# main.net
KiCad netlist of a schematic drawn in Altium Designer
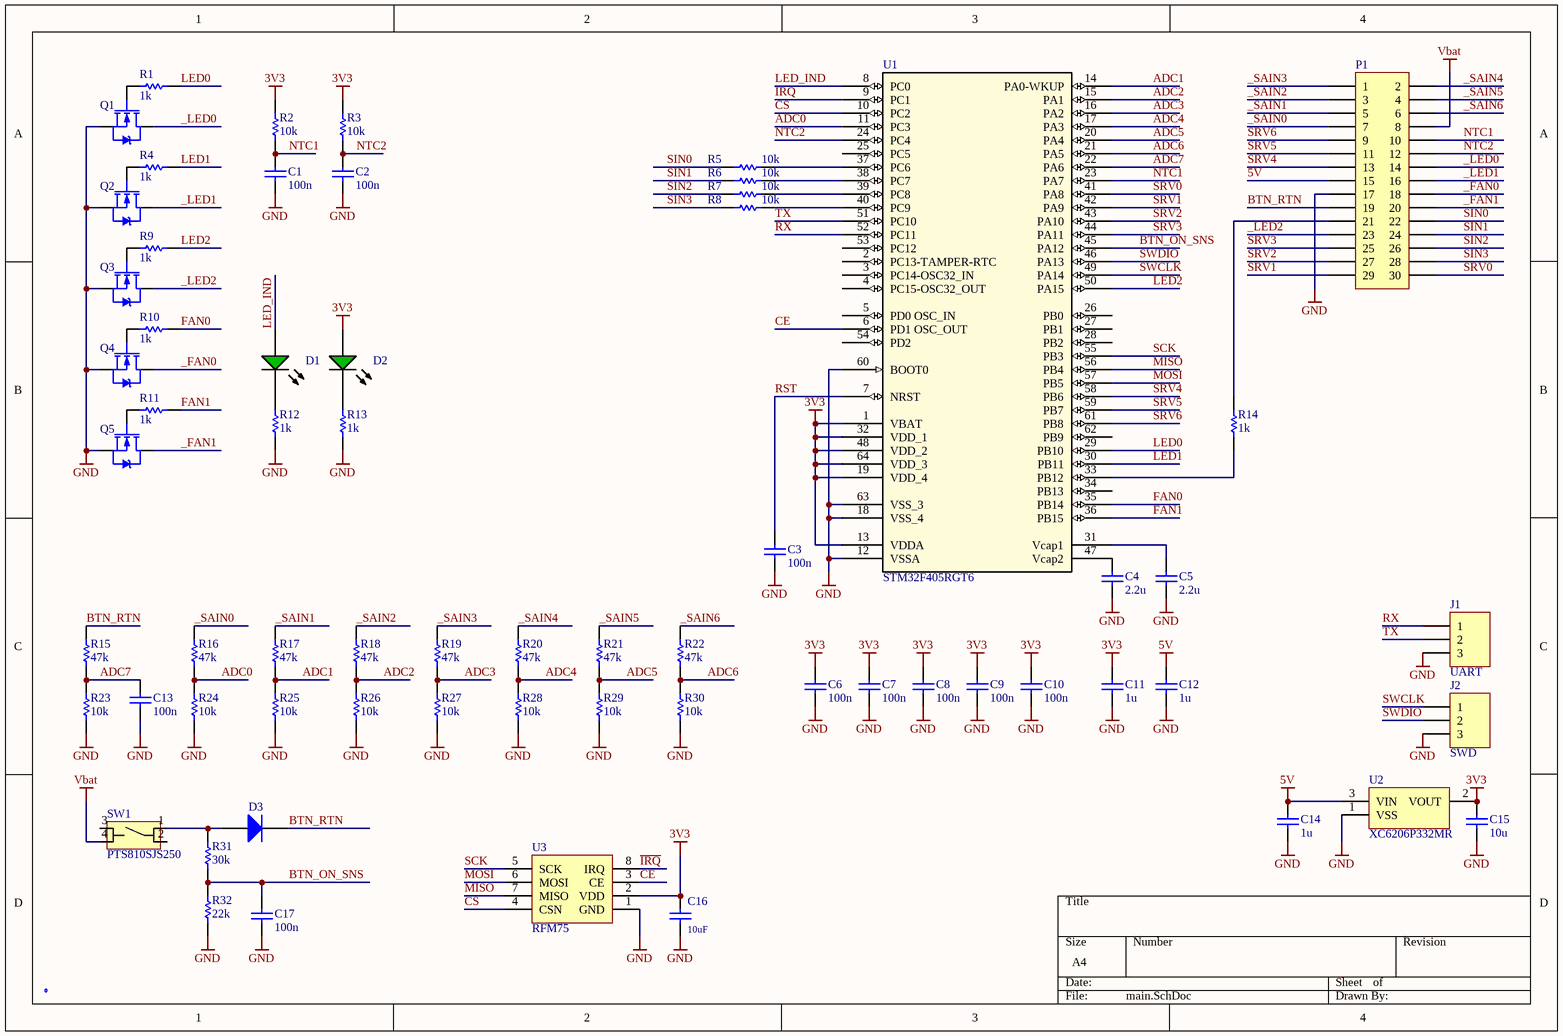
[diagram p0: main.SchDoc]

(export (version "E")
  (design (tool "Eeschema 10.0.6"))
  (components
    (comp (ref "C1")
      (value "100n")
      (footprint "C0603")
      (libsource (lib "Miscellaneous Devices") (part "Cap"))
    )
    (comp (ref "C2")
      (value "100n")
      (footprint "C0603")
      (libsource (lib "Miscellaneous Devices") (part "Cap"))
    )
    (comp (ref "C3")
      (value "100n")
      (footprint "C0402")
      (libsource (lib "Miscellaneous Devices") (part "Cap"))
    )
    (comp (ref "C4")
      (value "2.2u")
      (footprint "C0603")
      (libsource (lib "Miscellaneous Devices") (part "Cap"))
    )
    (comp (ref "C5")
      (value "2.2u")
      (footprint "C0603")
      (libsource (lib "Miscellaneous Devices") (part "Cap"))
    )
    (comp (ref "C6")
      (value "100n")
      (footprint "C0402")
      (libsource (lib "Miscellaneous Devices") (part "Cap"))
    )
    (comp (ref "C7")
      (value "100n")
      (footprint "C0402")
      (libsource (lib "Miscellaneous Devices") (part "Cap"))
    )
    (comp (ref "C8")
      (value "100n")
      (footprint "C0402")
      (libsource (lib "Miscellaneous Devices") (part "Cap"))
    )
    (comp (ref "C9")
      (value "100n")
      (footprint "C0402")
      (libsource (lib "Miscellaneous Devices") (part "Cap"))
    )
    (comp (ref "C10")
      (value "100n")
      (footprint "C0402")
      (libsource (lib "Miscellaneous Devices") (part "Cap"))
    )
    (comp (ref "C11") (value "1u") (footprint "C0603") (libsource (lib "Miscellaneous Devices") (part "Cap")))
    (comp (ref "C12") (value "1u") (footprint "C0603") (libsource (lib "Miscellaneous Devices") (part "Cap")))
    (comp (ref "C13")
      (value "100n")
      (footprint "C0402")
      (libsource (lib "Miscellaneous Devices") (part "Cap"))
    )
    (comp (ref "C14") (value "1u") (footprint "C1210") (libsource (lib "Miscellaneous Devices") (part "Cap")))
    (comp (ref "C15")
      (value "10u")
      (footprint "C1210")
      (libsource (lib "Miscellaneous Devices") (part "Cap"))
    )
    (comp (ref "C16")
      (value "10uF")
      (footprint "C0805")
      (libsource (lib "Miscellaneous Devices") (part "CAP"))
    )
    (comp (ref "C17")
      (value "100n")
      (footprint "C0402")
      (libsource (lib "Miscellaneous Devices") (part "Cap"))
    )
    (comp (ref "D1")
      (value "GRN")
      (footprint "LED-0603-GRN")
      (description "LED 0603 GRN")
      (fields (field (name "LCSC PART NUMBER") "C434420"))
      (libsource (lib "Miscellaneous Devices") (part "LED-0603-GREEN"))
    )
    (comp (ref "D2")
      (value "GRN")
      (footprint "LED-0603-GRN")
      (description "LED 0603 GRN")
      (fields (field (name "LCSC PART NUMBER") "C434420"))
      (libsource (lib "Miscellaneous Devices") (part "LED-0603-GREEN"))
    )
    (comp (ref "D3")
      (value "DS1M")
      (footprint "SOD-123FL")
      (libsource (lib "Miscellaneous Devices") (part "US1M-13-F"))
    )
    (comp (ref "J1")
      (value "UART")
      (footprint "HDR-1x3-P1.25")
      (libsource (lib "Miscellaneous Devices") (part "Header 3"))
    )
    (comp (ref "J2")
      (value "SWD")
      (footprint "HDR-1x3-P1.25")
      (libsource (lib "Miscellaneous Devices") (part "Header 3"))
    )
    (comp (ref "LOGO1") (value "LOGO") (footprint "LOGO") (libsource (lib "Schlib1") (part "LOGO")))
    (comp (ref "P1")
      (value "Header 15X2")
      (footprint "HDR2X15-2mm")
      (description "Header, 15-Pin, Dual row")
      (libsource (lib "Miscellaneous Connectors") (part "Header 15X2"))
    )
    (comp (ref "Q1")
      (value "IRLML2502")
      (footprint "SOT-23")
      (description "MOSFET N-CH 20V 4.2A SOT-23-3")
      (libsource (lib "RozumLibrary") (part "IRLML2502"))
    )
    (comp (ref "Q2")
      (value "IRLML2502")
      (footprint "SOT-23")
      (description "MOSFET N-CH 20V 4.2A SOT-23-3")
      (libsource (lib "RozumLibrary") (part "IRLML2502"))
    )
    (comp (ref "Q3")
      (value "IRLML2502")
      (footprint "SOT-23")
      (description "MOSFET N-CH 20V 4.2A SOT-23-3")
      (libsource (lib "RozumLibrary") (part "IRLML2502"))
    )
    (comp (ref "Q4")
      (value "IRLML2502")
      (footprint "SOT-23")
      (description "MOSFET N-CH 20V 4.2A SOT-23-3")
      (libsource (lib "RozumLibrary") (part "IRLML2502"))
    )
    (comp (ref "Q5")
      (value "IRLML2502")
      (footprint "SOT-23")
      (description "MOSFET N-CH 20V 4.2A SOT-23-3")
      (libsource (lib "RozumLibrary") (part "IRLML2502"))
    )
    (comp (ref "R1") (value "1k") (footprint "R0603") (libsource (lib "Miscellaneous Devices") (part "Res1")))
    (comp (ref "R2")
      (value "10k")
      (footprint "R0603")
      (libsource (lib "Miscellaneous Devices") (part "Res1"))
    )
    (comp (ref "R3")
      (value "10k")
      (footprint "R0603")
      (libsource (lib "Miscellaneous Devices") (part "Res1"))
    )
    (comp (ref "R4") (value "1k") (footprint "R0603") (libsource (lib "Miscellaneous Devices") (part "Res1")))
    (comp (ref "R5")
      (value "10k")
      (footprint "R0603")
      (libsource (lib "Miscellaneous Devices") (part "Res1"))
    )
    (comp (ref "R6")
      (value "10k")
      (footprint "R0603")
      (libsource (lib "Miscellaneous Devices") (part "Res1"))
    )
    (comp (ref "R7")
      (value "10k")
      (footprint "R0603")
      (libsource (lib "Miscellaneous Devices") (part "Res1"))
    )
    (comp (ref "R8")
      (value "10k")
      (footprint "R0603")
      (libsource (lib "Miscellaneous Devices") (part "Res1"))
    )
    (comp (ref "R9") (value "1k") (footprint "R0603") (libsource (lib "Miscellaneous Devices") (part "Res1")))
    (comp (ref "R10")
      (value "1k")
      (footprint "R0603")
      (libsource (lib "Miscellaneous Devices") (part "Res1"))
    )
    (comp (ref "R11")
      (value "1k")
      (footprint "R0603")
      (libsource (lib "Miscellaneous Devices") (part "Res1"))
    )
    (comp (ref "R12")
      (value "1k")
      (footprint "R0603")
      (libsource (lib "Miscellaneous Devices") (part "Res1"))
    )
    (comp (ref "R13")
      (value "1k")
      (footprint "R0603")
      (libsource (lib "Miscellaneous Devices") (part "Res1"))
    )
    (comp (ref "R14")
      (value "1k")
      (footprint "R0603")
      (libsource (lib "Miscellaneous Devices") (part "Res1"))
    )
    (comp (ref "R15")
      (value "47k")
      (footprint "R0603")
      (libsource (lib "Miscellaneous Devices") (part "Res1"))
    )
    (comp (ref "R16")
      (value "47k")
      (footprint "R0402")
      (libsource (lib "Miscellaneous Devices") (part "Res1"))
    )
    (comp (ref "R17")
      (value "47k")
      (footprint "R0402")
      (libsource (lib "Miscellaneous Devices") (part "Res1"))
    )
    (comp (ref "R18")
      (value "47k")
      (footprint "R0402")
      (libsource (lib "Miscellaneous Devices") (part "Res1"))
    )
    (comp (ref "R19")
      (value "47k")
      (footprint "R0402")
      (libsource (lib "Miscellaneous Devices") (part "Res1"))
    )
    (comp (ref "R20")
      (value "47k")
      (footprint "R0402")
      (libsource (lib "Miscellaneous Devices") (part "Res1"))
    )
    (comp (ref "R21")
      (value "47k")
      (footprint "R0603")
      (libsource (lib "Miscellaneous Devices") (part "Res1"))
    )
    (comp (ref "R22")
      (value "47k")
      (footprint "R0603")
      (libsource (lib "Miscellaneous Devices") (part "Res1"))
    )
    (comp (ref "R23")
      (value "10k")
      (footprint "R0603")
      (libsource (lib "Miscellaneous Devices") (part "Res1"))
    )
    (comp (ref "R24")
      (value "10k")
      (footprint "R0402")
      (libsource (lib "Miscellaneous Devices") (part "Res1"))
    )
    (comp (ref "R25")
      (value "10k")
      (footprint "R0402")
      (libsource (lib "Miscellaneous Devices") (part "Res1"))
    )
    (comp (ref "R26")
      (value "10k")
      (footprint "R0402")
      (libsource (lib "Miscellaneous Devices") (part "Res1"))
    )
    (comp (ref "R27")
      (value "10k")
      (footprint "R0402")
      (libsource (lib "Miscellaneous Devices") (part "Res1"))
    )
    (comp (ref "R28")
      (value "10k")
      (footprint "R0402")
      (libsource (lib "Miscellaneous Devices") (part "Res1"))
    )
    (comp (ref "R29")
      (value "10k")
      (footprint "R0603")
      (libsource (lib "Miscellaneous Devices") (part "Res1"))
    )
    (comp (ref "R30")
      (value "10k")
      (footprint "R0603")
      (libsource (lib "Miscellaneous Devices") (part "Res1"))
    )
    (comp (ref "R31")
      (value "30k")
      (footprint "R0603")
      (libsource (lib "Miscellaneous Devices") (part "Res1"))
    )
    (comp (ref "R32")
      (value "22k")
      (footprint "R0603")
      (libsource (lib "Miscellaneous Devices") (part "Res1"))
    )
    (comp (ref "SW1")
      (value "PTS810SJS250")
      (footprint "BTN_PTS810")
      (fields (field (name "LCSC PART NUMBER") "C221896"))
      (libsource (lib "Miscellaneous Devices") (part "Component_1"))
    )
    (comp (ref "U1")
      (value "STM32F405RGT6")
      (footprint "LQFP-64")
      (description "MCU STM32F405RGT6")
      (libsource (lib "RozumLibrary") (part "STM32F405RGT6"))
    )
    (comp (ref "U2")
      (value "XC6206P332MR")
      (footprint "SOT-23")
      (fields (field (name "LCSC PART NUMBER") "C347376"))
      (libsource (lib "Schlib1") (part "Component_4_1"))
    )
    (comp (ref "U3") (value "RFM75") (footprint "RFM75") (libsource (lib "Schlib1") (part "RFM75")))
  )
  (nets
    (net (code "1") (name "/ADC0") (class "Default")
      (node (ref "R16") (pin "1") (pinfunction "1_1") (pintype "passive"))
      (node (ref "R24") (pin "2") (pinfunction "2_2") (pintype "passive"))
      (node (ref "U1") (pin "11") (pinfunction "PC3_11") (pintype "bidirectional"))
    )
    (net (code "2") (name "/ADC1") (class "Default")
      (node (ref "R17") (pin "1") (pinfunction "1_1") (pintype "passive"))
      (node (ref "R25") (pin "2") (pinfunction "2_2") (pintype "passive"))
      (node (ref "U1") (pin "14") (pinfunction "PA0-WKUP_14") (pintype "bidirectional"))
    )
    (net (code "3") (name "/ADC2") (class "Default")
      (node (ref "R18") (pin "1") (pinfunction "1_1") (pintype "passive"))
      (node (ref "R26") (pin "2") (pinfunction "2_2") (pintype "passive"))
      (node (ref "U1") (pin "15") (pinfunction "PA1_15") (pintype "bidirectional"))
    )
    (net (code "4") (name "/ADC3") (class "Default")
      (node (ref "R19") (pin "1") (pinfunction "1_1") (pintype "passive"))
      (node (ref "R27") (pin "2") (pinfunction "2_2") (pintype "passive"))
      (node (ref "U1") (pin "16") (pinfunction "PA2_16") (pintype "bidirectional"))
    )
    (net (code "5") (name "/ADC4") (class "Default")
      (node (ref "R20") (pin "1") (pinfunction "1_1") (pintype "passive"))
      (node (ref "R28") (pin "2") (pinfunction "2_2") (pintype "passive"))
      (node (ref "U1") (pin "17") (pinfunction "PA3_17") (pintype "bidirectional"))
    )
    (net (code "6") (name "/ADC5") (class "Default")
      (node (ref "R21") (pin "1") (pinfunction "1_1") (pintype "passive"))
      (node (ref "R29") (pin "2") (pinfunction "2_2") (pintype "passive"))
      (node (ref "U1") (pin "20") (pinfunction "PA4_20") (pintype "bidirectional"))
    )
    (net (code "7") (name "/ADC6") (class "Default")
      (node (ref "R22") (pin "1") (pinfunction "1_1") (pintype "passive"))
      (node (ref "R30") (pin "2") (pinfunction "2_2") (pintype "passive"))
      (node (ref "U1") (pin "21") (pinfunction "PA5_21") (pintype "bidirectional"))
    )
    (net (code "8") (name "/ADC7") (class "Default")
      (node (ref "C13") (pin "2") (pinfunction "2_2") (pintype "passive"))
      (node (ref "R15") (pin "1") (pinfunction "1_1") (pintype "passive"))
      (node (ref "R23") (pin "2") (pinfunction "2_2") (pintype "passive"))
      (node (ref "U1") (pin "22") (pinfunction "PA6_22") (pintype "bidirectional"))
    )
    (net (code "9") (name "/BTN_ON_SNS") (class "Default")
      (node (ref "C17") (pin "2") (pinfunction "2_2") (pintype "passive"))
      (node (ref "R31") (pin "1") (pinfunction "1_1") (pintype "passive"))
      (node (ref "R32") (pin "2") (pinfunction "2_2") (pintype "passive"))
      (node (ref "U1") (pin "45") (pinfunction "PA12_45") (pintype "bidirectional"))
    )
    (net (code "10") (name "/BTN_RTN") (class "Default")
      (node (ref "D3") (pin "2") (pinfunction "K_2") (pintype "passive"))
      (node (ref "P1") (pin "19") (pinfunction "19_19") (pintype "passive"))
      (node (ref "R15") (pin "2") (pinfunction "2_2") (pintype "passive"))
    )
    (net (code "11") (name "/CE") (class "Default")
      (node (ref "U1") (pin "6") (pinfunction "PD1_OSC_OUT_6") (pintype "bidirectional"))
      (node (ref "U3") (pin "3") (pinfunction "CE_3") (pintype "passive"))
    )
    (net (code "12") (name "/FAN0") (class "Default")
      (node (ref "R10") (pin "2") (pinfunction "2_2") (pintype "passive"))
      (node (ref "U1") (pin "35") (pinfunction "PB14_35") (pintype "bidirectional"))
    )
    (net (code "13") (name "/FAN1") (class "Default")
      (node (ref "R11") (pin "2") (pinfunction "2_2") (pintype "passive"))
      (node (ref "U1") (pin "36") (pinfunction "PB15_36") (pintype "bidirectional"))
    )
    (net (code "14") (name "/LED0") (class "Default")
      (node (ref "R1") (pin "2") (pinfunction "2_2") (pintype "passive"))
      (node (ref "U1") (pin "29") (pinfunction "PB10_29") (pintype "bidirectional"))
    )
    (net (code "15") (name "/LED1") (class "Default")
      (node (ref "R4") (pin "2") (pinfunction "2_2") (pintype "passive"))
      (node (ref "U1") (pin "30") (pinfunction "PB11_30") (pintype "bidirectional"))
    )
    (net (code "16") (name "/LED2") (class "Default")
      (node (ref "R9") (pin "2") (pinfunction "2_2") (pintype "passive"))
      (node (ref "U1") (pin "50") (pinfunction "PA15_50") (pintype "bidirectional"))
    )
    (net (code "17") (name "/LED_IND") (class "Default")
      (node (ref "D1") (pin "1") (pinfunction "A_1") (pintype "passive"))
      (node (ref "U1") (pin "8") (pinfunction "PC0_8") (pintype "bidirectional"))
    )
    (net (code "18") (name "/MISO") (class "Default")
      (node (ref "U1") (pin "56") (pinfunction "PB4_56") (pintype "bidirectional"))
      (node (ref "U3") (pin "7") (pinfunction "MISO_7") (pintype "passive"))
    )
    (net (code "19") (name "/MOSI") (class "Default")
      (node (ref "U1") (pin "57") (pinfunction "PB5_57") (pintype "bidirectional"))
      (node (ref "U3") (pin "6") (pinfunction "MOSI_6") (pintype "passive"))
    )
    (net (code "20") (name "/NTC1") (class "Default")
      (node (ref "C1") (pin "2") (pinfunction "2_2") (pintype "passive"))
      (node (ref "P1") (pin "10") (pinfunction "10_10") (pintype "passive"))
      (node (ref "R2") (pin "1") (pinfunction "1_1") (pintype "passive"))
      (node (ref "U1") (pin "23") (pinfunction "PA7_23") (pintype "bidirectional"))
    )
    (net (code "21") (name "/NTC2") (class "Default")
      (node (ref "C2") (pin "2") (pinfunction "2_2") (pintype "passive"))
      (node (ref "P1") (pin "12") (pinfunction "12_12") (pintype "passive"))
      (node (ref "R3") (pin "1") (pinfunction "1_1") (pintype "passive"))
      (node (ref "U1") (pin "24") (pinfunction "PC4_24") (pintype "bidirectional"))
    )
    (net (code "22") (name "/RST") (class "Default")
      (node (ref "C3") (pin "2") (pinfunction "2_2") (pintype "passive"))
      (node (ref "U1") (pin "7") (pinfunction "NRST_7") (pintype "bidirectional"))
    )
    (net (code "23") (name "/RX") (class "Default")
      (node (ref "J1") (pin "1") (pinfunction "1_1") (pintype "passive"))
      (node (ref "U1") (pin "52") (pinfunction "PC11_52") (pintype "bidirectional"))
    )
    (net (code "24") (name "/SCK") (class "Default")
      (node (ref "U1") (pin "55") (pinfunction "PB3_55") (pintype "bidirectional"))
      (node (ref "U3") (pin "5") (pinfunction "SCK_5") (pintype "passive"))
    )
    (net (code "25") (name "/SIN0") (class "Default")
      (node (ref "P1") (pin "22") (pinfunction "22_22") (pintype "passive"))
      (node (ref "R5") (pin "2") (pinfunction "2_2") (pintype "passive"))
    )
    (net (code "26") (name "/SIN1") (class "Default")
      (node (ref "P1") (pin "24") (pinfunction "24_24") (pintype "passive"))
      (node (ref "R6") (pin "2") (pinfunction "2_2") (pintype "passive"))
    )
    (net (code "27") (name "/SIN2") (class "Default")
      (node (ref "P1") (pin "26") (pinfunction "26_26") (pintype "passive"))
      (node (ref "R7") (pin "2") (pinfunction "2_2") (pintype "passive"))
    )
    (net (code "28") (name "/SIN3") (class "Default")
      (node (ref "P1") (pin "28") (pinfunction "28_28") (pintype "passive"))
      (node (ref "R8") (pin "2") (pinfunction "2_2") (pintype "passive"))
    )
    (net (code "29") (name "/SRV0") (class "Default")
      (node (ref "P1") (pin "30") (pinfunction "30_30") (pintype "passive"))
      (node (ref "U1") (pin "41") (pinfunction "PA8_41") (pintype "bidirectional"))
    )
    (net (code "30") (name "/SRV1") (class "Default")
      (node (ref "P1") (pin "29") (pinfunction "29_29") (pintype "passive"))
      (node (ref "U1") (pin "42") (pinfunction "PA9_42") (pintype "bidirectional"))
    )
    (net (code "31") (name "/SRV2") (class "Default")
      (node (ref "P1") (pin "27") (pinfunction "27_27") (pintype "passive"))
      (node (ref "U1") (pin "43") (pinfunction "PA10_43") (pintype "bidirectional"))
    )
    (net (code "32") (name "/SRV3") (class "Default")
      (node (ref "P1") (pin "25") (pinfunction "25_25") (pintype "passive"))
      (node (ref "U1") (pin "44") (pinfunction "PA11_44") (pintype "bidirectional"))
    )
    (net (code "33") (name "/SRV4") (class "Default")
      (node (ref "P1") (pin "13") (pinfunction "13_13") (pintype "passive"))
      (node (ref "U1") (pin "58") (pinfunction "PB6_58") (pintype "bidirectional"))
    )
    (net (code "34") (name "/SRV5") (class "Default")
      (node (ref "P1") (pin "11") (pinfunction "11_11") (pintype "passive"))
      (node (ref "U1") (pin "59") (pinfunction "PB7_59") (pintype "bidirectional"))
    )
    (net (code "35") (name "/SRV6") (class "Default")
      (node (ref "P1") (pin "9") (pinfunction "9_9") (pintype "passive"))
      (node (ref "U1") (pin "61") (pinfunction "PB8_61") (pintype "bidirectional"))
    )
    (net (code "36") (name "/SWCLK") (class "Default")
      (node (ref "J2") (pin "1") (pinfunction "1_1") (pintype "passive"))
      (node (ref "U1") (pin "49") (pinfunction "PA14_49") (pintype "bidirectional"))
    )
    (net (code "37") (name "/SWDIO") (class "Default")
      (node (ref "J2") (pin "2") (pinfunction "2_2") (pintype "passive"))
      (node (ref "U1") (pin "46") (pinfunction "PA13_46") (pintype "bidirectional"))
    )
    (net (code "38") (name "/TX") (class "Default")
      (node (ref "J1") (pin "2") (pinfunction "2_2") (pintype "passive"))
      (node (ref "U1") (pin "51") (pinfunction "PC10_51") (pintype "bidirectional"))
    )
    (net (code "39") (name "/_FAN0") (class "Default")
      (node (ref "P1") (pin "18") (pinfunction "18_18") (pintype "passive"))
      (node (ref "Q4") (pin "3") (pinfunction "D_3") (pintype "passive"))
    )
    (net (code "40") (name "/_FAN1") (class "Default")
      (node (ref "P1") (pin "20") (pinfunction "20_20") (pintype "passive"))
      (node (ref "Q5") (pin "3") (pinfunction "D_3") (pintype "passive"))
    )
    (net (code "41") (name "/_LED0") (class "Default")
      (node (ref "P1") (pin "14") (pinfunction "14_14") (pintype "passive"))
      (node (ref "Q1") (pin "3") (pinfunction "D_3") (pintype "passive"))
    )
    (net (code "42") (name "/_LED1") (class "Default")
      (node (ref "P1") (pin "16") (pinfunction "16_16") (pintype "passive"))
      (node (ref "Q2") (pin "3") (pinfunction "D_3") (pintype "passive"))
    )
    (net (code "43") (name "/_LED2") (class "Default")
      (node (ref "P1") (pin "23") (pinfunction "23_23") (pintype "passive"))
      (node (ref "Q3") (pin "3") (pinfunction "D_3") (pintype "passive"))
    )
    (net (code "44") (name "/_SAIN0") (class "Default")
      (node (ref "P1") (pin "7") (pinfunction "7_7") (pintype "passive"))
      (node (ref "R16") (pin "2") (pinfunction "2_2") (pintype "passive"))
    )
    (net (code "45") (name "/_SAIN1") (class "Default")
      (node (ref "P1") (pin "5") (pinfunction "5_5") (pintype "passive"))
      (node (ref "R17") (pin "2") (pinfunction "2_2") (pintype "passive"))
    )
    (net (code "46") (name "/_SAIN2") (class "Default")
      (node (ref "P1") (pin "3") (pinfunction "3_3") (pintype "passive"))
      (node (ref "R18") (pin "2") (pinfunction "2_2") (pintype "passive"))
    )
    (net (code "47") (name "/_SAIN3") (class "Default")
      (node (ref "P1") (pin "1") (pinfunction "1_1") (pintype "passive"))
      (node (ref "R19") (pin "2") (pinfunction "2_2") (pintype "passive"))
    )
    (net (code "48") (name "/_SAIN4") (class "Default")
      (node (ref "P1") (pin "2") (pinfunction "2_2") (pintype "passive"))
      (node (ref "R20") (pin "2") (pinfunction "2_2") (pintype "passive"))
    )
    (net (code "49") (name "/_SAIN5") (class "Default")
      (node (ref "P1") (pin "4") (pinfunction "4_4") (pintype "passive"))
      (node (ref "R21") (pin "2") (pinfunction "2_2") (pintype "passive"))
    )
    (net (code "50") (name "/_SAIN6") (class "Default")
      (node (ref "P1") (pin "6") (pinfunction "6_6") (pintype "passive"))
      (node (ref "R22") (pin "2") (pinfunction "2_2") (pintype "passive"))
    )
    (net (code "51") (name "/~{CS}") (class "Default")
      (node (ref "U1") (pin "10") (pinfunction "PC2_10") (pintype "bidirectional"))
      (node (ref "U3") (pin "4") (pinfunction "CSN_4") (pintype "passive"))
    )
    (net (code "52") (name "/~{IRQ}") (class "Default")
      (node (ref "U1") (pin "9") (pinfunction "PC1_9") (pintype "bidirectional"))
      (node (ref "U3") (pin "8") (pinfunction "IRQ_8") (pintype "passive"))
    )
    (net (code "53") (name "3V3") (class "Default")
      (node (ref "C10") (pin "2") (pinfunction "2_2") (pintype "passive"))
      (node (ref "C11") (pin "2") (pinfunction "2_2") (pintype "passive"))
      (node (ref "C15") (pin "2") (pinfunction "2_2") (pintype "passive"))
      (node (ref "C16") (pin "2") (pinfunction "2_2") (pintype "passive"))
      (node (ref "C6") (pin "2") (pinfunction "2_2") (pintype "passive"))
      (node (ref "C7") (pin "2") (pinfunction "2_2") (pintype "passive"))
      (node (ref "C8") (pin "2") (pinfunction "2_2") (pintype "passive"))
      (node (ref "C9") (pin "2") (pinfunction "2_2") (pintype "passive"))
      (node (ref "D2") (pin "1") (pinfunction "A_1") (pintype "passive"))
      (node (ref "R2") (pin "2") (pinfunction "2_2") (pintype "passive"))
      (node (ref "R3") (pin "2") (pinfunction "2_2") (pintype "passive"))
      (node (ref "U1") (pin "1") (pinfunction "VBAT_1") (pintype "power_in"))
      (node (ref "U1") (pin "13") (pinfunction "VDDA_13") (pintype "power_in"))
      (node (ref "U1") (pin "19") (pinfunction "VDD_4_19") (pintype "power_in"))
      (node (ref "U1") (pin "32") (pinfunction "VDD_1_32") (pintype "power_in"))
      (node (ref "U1") (pin "48") (pinfunction "VDD_2_48") (pintype "power_in"))
      (node (ref "U1") (pin "64") (pinfunction "VDD_3_64") (pintype "power_in"))
      (node (ref "U2") (pin "2") (pinfunction "VOUT_2") (pintype "passive"))
      (node (ref "U3") (pin "2") (pinfunction "VDD_2") (pintype "passive"))
    )
    (net (code "54") (name "5V") (class "Default")
      (node (ref "C12") (pin "2") (pinfunction "2_2") (pintype "passive"))
      (node (ref "C14") (pin "2") (pinfunction "2_2") (pintype "passive"))
      (node (ref "P1") (pin "15") (pinfunction "15_15") (pintype "passive"))
      (node (ref "U2") (pin "3") (pinfunction "VIN_3") (pintype "passive"))
    )
    (net (code "55") (name "GND") (class "Default")
      (node (ref "C1") (pin "1") (pinfunction "1_1") (pintype "passive"))
      (node (ref "C10") (pin "1") (pinfunction "1_1") (pintype "passive"))
      (node (ref "C11") (pin "1") (pinfunction "1_1") (pintype "passive"))
      (node (ref "C12") (pin "1") (pinfunction "1_1") (pintype "passive"))
      (node (ref "C13") (pin "1") (pinfunction "1_1") (pintype "passive"))
      (node (ref "C14") (pin "1") (pinfunction "1_1") (pintype "passive"))
      (node (ref "C15") (pin "1") (pinfunction "1_1") (pintype "passive"))
      (node (ref "C16") (pin "1") (pinfunction "1_1") (pintype "passive"))
      (node (ref "C17") (pin "1") (pinfunction "1_1") (pintype "passive"))
      (node (ref "C2") (pin "1") (pinfunction "1_1") (pintype "passive"))
      (node (ref "C3") (pin "1") (pinfunction "1_1") (pintype "passive"))
      (node (ref "C4") (pin "1") (pinfunction "1_1") (pintype "passive"))
      (node (ref "C5") (pin "1") (pinfunction "1_1") (pintype "passive"))
      (node (ref "C6") (pin "1") (pinfunction "1_1") (pintype "passive"))
      (node (ref "C7") (pin "1") (pinfunction "1_1") (pintype "passive"))
      (node (ref "C8") (pin "1") (pinfunction "1_1") (pintype "passive"))
      (node (ref "C9") (pin "1") (pinfunction "1_1") (pintype "passive"))
      (node (ref "J1") (pin "3") (pinfunction "3_3") (pintype "passive"))
      (node (ref "J2") (pin "3") (pinfunction "3_3") (pintype "passive"))
      (node (ref "P1") (pin "17") (pinfunction "17_17") (pintype "passive"))
      (node (ref "Q1") (pin "2") (pinfunction "S_2") (pintype "passive"))
      (node (ref "Q2") (pin "2") (pinfunction "S_2") (pintype "passive"))
      (node (ref "Q3") (pin "2") (pinfunction "S_2") (pintype "passive"))
      (node (ref "Q4") (pin "2") (pinfunction "S_2") (pintype "passive"))
      (node (ref "Q5") (pin "2") (pinfunction "S_2") (pintype "passive"))
      (node (ref "R12") (pin "1") (pinfunction "1_1") (pintype "passive"))
      (node (ref "R13") (pin "1") (pinfunction "1_1") (pintype "passive"))
      (node (ref "R23") (pin "1") (pinfunction "1_1") (pintype "passive"))
      (node (ref "R24") (pin "1") (pinfunction "1_1") (pintype "passive"))
      (node (ref "R25") (pin "1") (pinfunction "1_1") (pintype "passive"))
      (node (ref "R26") (pin "1") (pinfunction "1_1") (pintype "passive"))
      (node (ref "R27") (pin "1") (pinfunction "1_1") (pintype "passive"))
      (node (ref "R28") (pin "1") (pinfunction "1_1") (pintype "passive"))
      (node (ref "R29") (pin "1") (pinfunction "1_1") (pintype "passive"))
      (node (ref "R30") (pin "1") (pinfunction "1_1") (pintype "passive"))
      (node (ref "R32") (pin "1") (pinfunction "1_1") (pintype "passive"))
      (node (ref "U1") (pin "12") (pinfunction "VSSA_12") (pintype "power_in"))
      (node (ref "U1") (pin "18") (pinfunction "VSS_4_18") (pintype "power_in"))
      (node (ref "U1") (pin "60") (pinfunction "BOOT0_60") (pintype "input"))
      (node (ref "U1") (pin "63") (pinfunction "VSS_3_63") (pintype "power_in"))
      (node (ref "U2") (pin "1") (pinfunction "VSS_1") (pintype "passive"))
      (node (ref "U3") (pin "1") (pinfunction "GND_1") (pintype "passive"))
    )
    (net (code "56") (name "Net-(D1-K)") (class "Default")
      (node (ref "D1") (pin "2") (pinfunction "K_2") (pintype "passive"))
      (node (ref "R12") (pin "2") (pinfunction "2_2") (pintype "passive"))
    )
    (net (code "57") (name "Net-(D2-K)") (class "Default")
      (node (ref "D2") (pin "2") (pinfunction "K_2") (pintype "passive"))
      (node (ref "R13") (pin "2") (pinfunction "2_2") (pintype "passive"))
    )
    (net (code "58") (name "Net-(D3-A)") (class "Default")
      (node (ref "D3") (pin "1") (pinfunction "A_1") (pintype "passive"))
      (node (ref "R31") (pin "2") (pinfunction "2_2") (pintype "passive"))
      (node (ref "SW1") (pin "1") (pinfunction "1_1") (pintype "passive"))
    )
    (net (code "59") (name "Net-(P1-Pad21)") (class "Default")
      (node (ref "P1") (pin "21") (pinfunction "21_21") (pintype "passive"))
      (node (ref "R14") (pin "2") (pinfunction "2_2") (pintype "passive"))
    )
    (net (code "60") (name "Net-(Q1-G)") (class "Default")
      (node (ref "Q1") (pin "1") (pinfunction "G_1") (pintype "passive"))
      (node (ref "R1") (pin "1") (pinfunction "1_1") (pintype "passive"))
    )
    (net (code "61") (name "Net-(Q2-G)") (class "Default")
      (node (ref "Q2") (pin "1") (pinfunction "G_1") (pintype "passive"))
      (node (ref "R4") (pin "1") (pinfunction "1_1") (pintype "passive"))
    )
    (net (code "62") (name "Net-(Q3-G)") (class "Default")
      (node (ref "Q3") (pin "1") (pinfunction "G_1") (pintype "passive"))
      (node (ref "R9") (pin "1") (pinfunction "1_1") (pintype "passive"))
    )
    (net (code "63") (name "Net-(Q4-G)") (class "Default")
      (node (ref "Q4") (pin "1") (pinfunction "G_1") (pintype "passive"))
      (node (ref "R10") (pin "1") (pinfunction "1_1") (pintype "passive"))
    )
    (net (code "64") (name "Net-(Q5-G)") (class "Default")
      (node (ref "Q5") (pin "1") (pinfunction "G_1") (pintype "passive"))
      (node (ref "R11") (pin "1") (pinfunction "1_1") (pintype "passive"))
    )
    (net (code "65") (name "Net-(U1-PB12)") (class "Default")
      (node (ref "R14") (pin "1") (pinfunction "1_1") (pintype "passive"))
      (node (ref "U1") (pin "33") (pinfunction "PB12_33") (pintype "bidirectional"))
    )
    (net (code "66") (name "Net-(U1-PC6)") (class "Default")
      (node (ref "R5") (pin "1") (pinfunction "1_1") (pintype "passive"))
      (node (ref "U1") (pin "37") (pinfunction "PC6_37") (pintype "bidirectional"))
    )
    (net (code "67") (name "Net-(U1-PC7)") (class "Default")
      (node (ref "R6") (pin "1") (pinfunction "1_1") (pintype "passive"))
      (node (ref "U1") (pin "38") (pinfunction "PC7_38") (pintype "bidirectional"))
    )
    (net (code "68") (name "Net-(U1-PC8)") (class "Default")
      (node (ref "R7") (pin "1") (pinfunction "1_1") (pintype "passive"))
      (node (ref "U1") (pin "39") (pinfunction "PC8_39") (pintype "bidirectional"))
    )
    (net (code "69") (name "Net-(U1-PC9)") (class "Default")
      (node (ref "R8") (pin "1") (pinfunction "1_1") (pintype "passive"))
      (node (ref "U1") (pin "40") (pinfunction "PC9_40") (pintype "bidirectional"))
    )
    (net (code "70") (name "Net-(U1-Vcap1)") (class "Default")
      (node (ref "C5") (pin "2") (pinfunction "2_2") (pintype "passive"))
      (node (ref "U1") (pin "31") (pinfunction "Vcap1_31") (pintype "power_in"))
    )
    (net (code "71") (name "Net-(U1-Vcap2)") (class "Default")
      (node (ref "C4") (pin "2") (pinfunction "2_2") (pintype "passive"))
      (node (ref "U1") (pin "47") (pinfunction "Vcap2_47") (pintype "power_in"))
    )
    (net (code "72") (name "Vbat") (class "Default")
      (node (ref "P1") (pin "8") (pinfunction "8_8") (pintype "passive"))
      (node (ref "SW1") (pin "4") (pinfunction "4_4") (pintype "passive"))
    )
    (net (code "73") (name "unconnected-(SW1-Pad2)") (class "Default")
      (node (ref "SW1") (pin "2") (pinfunction "2_2") (pintype "passive"))
    )
    (net (code "74") (name "unconnected-(SW1-Pad3)") (class "Default")
      (node (ref "SW1") (pin "3") (pinfunction "3_3") (pintype "passive"))
    )
    (net (code "75") (name "unconnected-(U1-PB0-Pad26)") (class "Default")
      (node (ref "U1") (pin "26") (pinfunction "PB0_26") (pintype "bidirectional"))
    )
    (net (code "76") (name "unconnected-(U1-PB1-Pad27)") (class "Default")
      (node (ref "U1") (pin "27") (pinfunction "PB1_27") (pintype "bidirectional"))
    )
    (net (code "77") (name "unconnected-(U1-PB2-Pad28)") (class "Default")
      (node (ref "U1") (pin "28") (pinfunction "PB2_28") (pintype "bidirectional"))
    )
    (net (code "78") (name "unconnected-(U1-PB9-Pad62)") (class "Default")
      (node (ref "U1") (pin "62") (pinfunction "PB9_62") (pintype "bidirectional"))
    )
    (net (code "79") (name "unconnected-(U1-PB13-Pad34)") (class "Default")
      (node (ref "U1") (pin "34") (pinfunction "PB13_34") (pintype "bidirectional"))
    )
    (net (code "80") (name "unconnected-(U1-PC5-Pad25)") (class "Default")
      (node (ref "U1") (pin "25") (pinfunction "PC5_25") (pintype "bidirectional"))
    )
    (net (code "81") (name "unconnected-(U1-PC12-Pad53)") (class "Default")
      (node (ref "U1") (pin "53") (pinfunction "PC12_53") (pintype "bidirectional"))
    )
    (net (code "82") (name "unconnected-(U1-PC13-TAMPER-RTC-Pad2)") (class "Default")
      (node (ref "U1") (pin "2") (pinfunction "PC13-TAMPER-RTC_2") (pintype "bidirectional"))
    )
    (net (code "83") (name "unconnected-(U1-PC14-OSC32_IN-Pad3)") (class "Default")
      (node (ref "U1") (pin "3") (pinfunction "PC14-OSC32_IN_3") (pintype "bidirectional"))
    )
    (net (code "84") (name "unconnected-(U1-PC15-OSC32_OUT-Pad4)") (class "Default")
      (node (ref "U1") (pin "4") (pinfunction "PC15-OSC32_OUT_4") (pintype "bidirectional"))
    )
    (net (code "85") (name "unconnected-(U1-PD0_OSC_IN-Pad5)") (class "Default")
      (node (ref "U1") (pin "5") (pinfunction "PD0_OSC_IN_5") (pintype "bidirectional"))
    )
    (net (code "86") (name "unconnected-(U1-PD2-Pad54)") (class "Default")
      (node (ref "U1") (pin "54") (pinfunction "PD2_54") (pintype "bidirectional"))
    )
  )
)
